# rgbboard.net
KiCad netlist of a schematic drawn in EAGLE
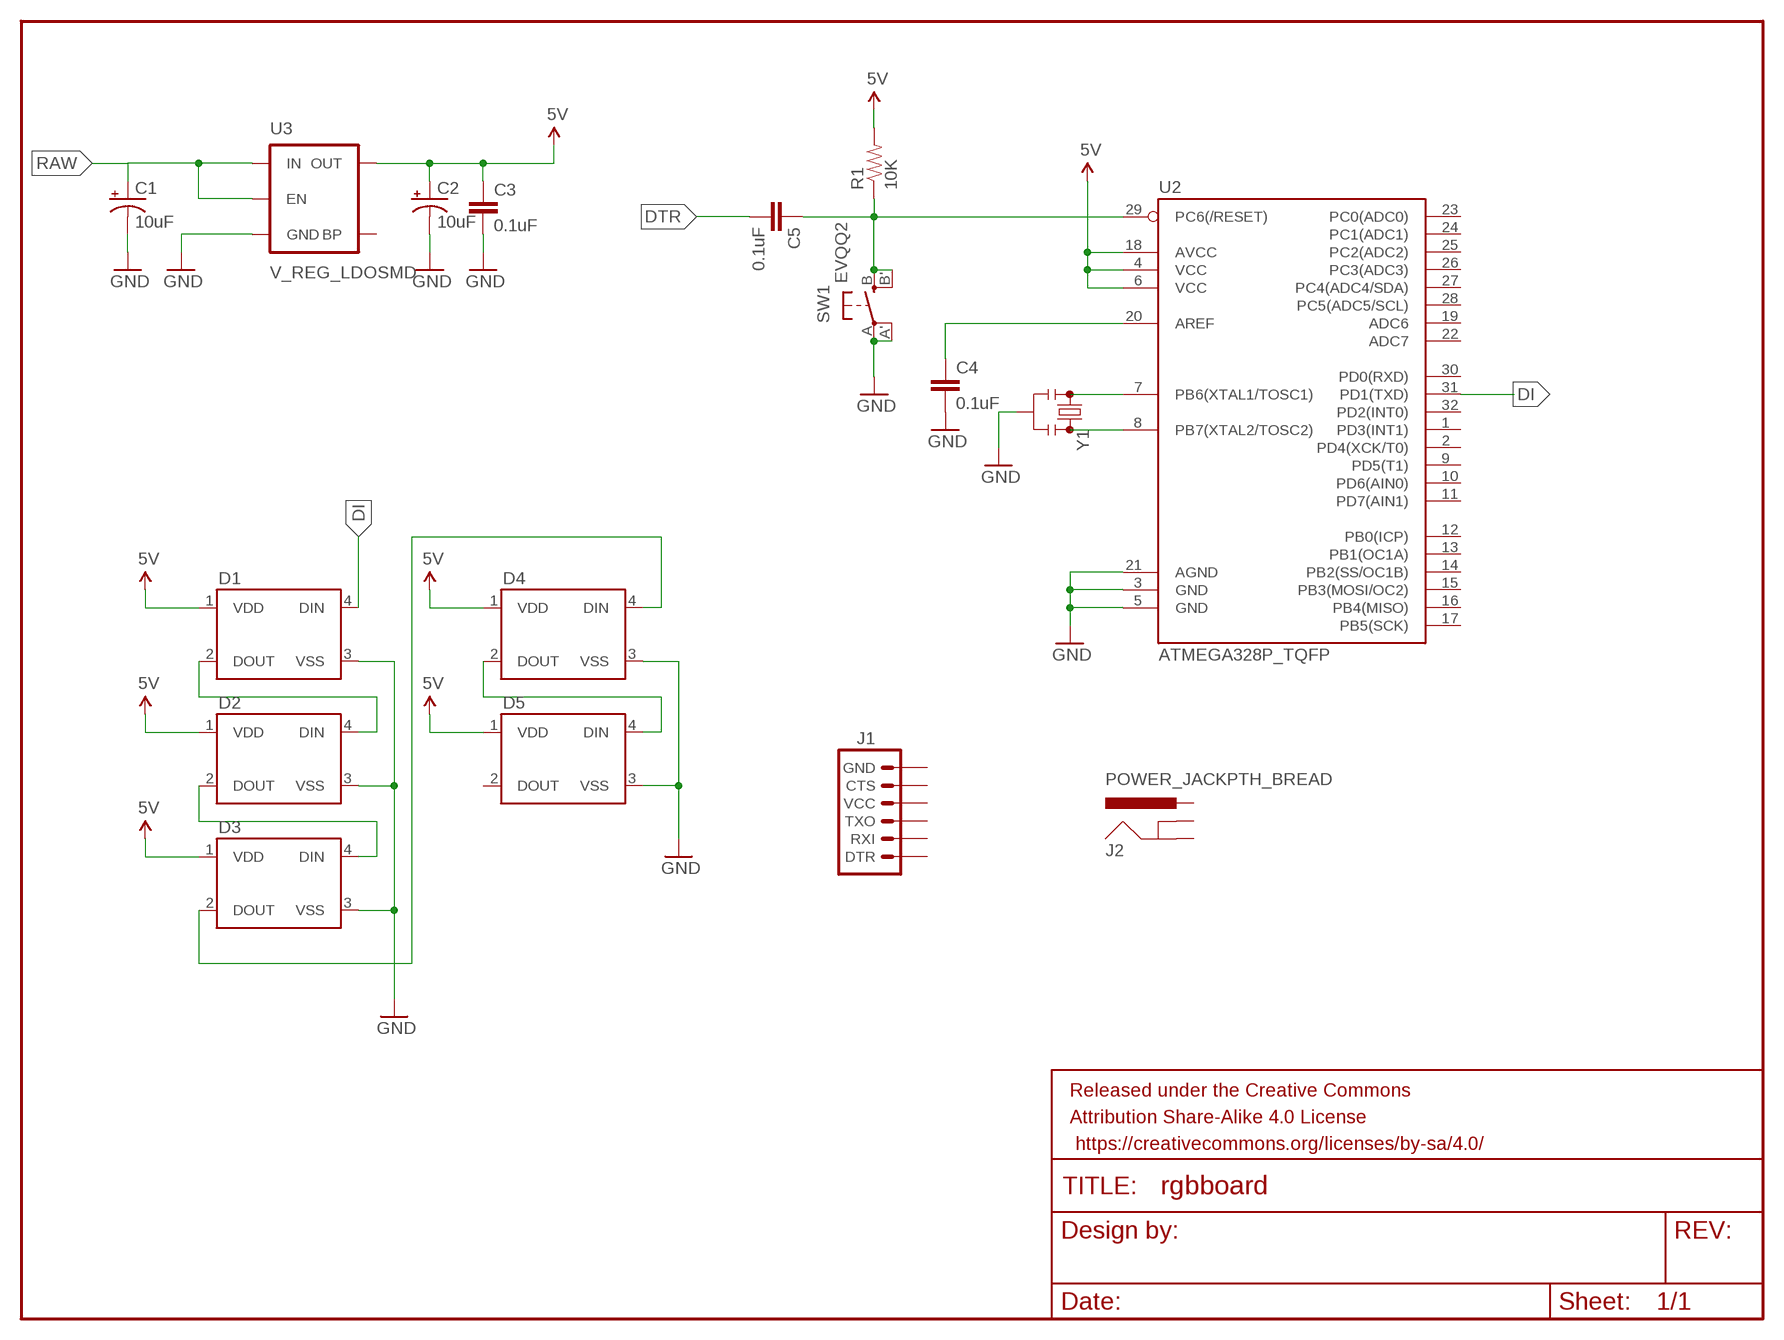
[diagram p0: schematic, sheet 1]

(export (version "E")
  (design (tool "Eeschema 10.0.6"))
  (components
    (comp (ref "C1")
      (value "10uF")
      (footprint "eagle-import:EIA3216")
      (libsource (lib "eagle-import") (part "CAP_POL1206"))
    )
    (comp (ref "C2")
      (value "10uF")
      (footprint "eagle-import:EIA3216")
      (libsource (lib "eagle-import") (part "CAP_POL1206"))
    )
    (comp (ref "C3")
      (value "0.1uF")
      (footprint "eagle-import:0603-CAP")
      (libsource (lib "eagle-import") (part "CAP0603-CAP"))
    )
    (comp (ref "C4")
      (value "0.1uF")
      (footprint "eagle-import:0603-CAP")
      (libsource (lib "eagle-import") (part "CAP0603-CAP"))
    )
    (comp (ref "C5")
      (value "0.1uF")
      (footprint "eagle-import:0603-CAP")
      (libsource (lib "eagle-import") (part "CAP0603-CAP"))
    )
    (comp (ref "D1")
      (value "WS2812B")
      (footprint "eagle-import:WS2812B")
      (libsource (lib "eagle-import") (part "WS2812B"))
    )
    (comp (ref "D2")
      (value "WS2812B")
      (footprint "eagle-import:WS2812B")
      (libsource (lib "eagle-import") (part "WS2812B"))
    )
    (comp (ref "D3")
      (value "WS2812B")
      (footprint "eagle-import:WS2812B")
      (libsource (lib "eagle-import") (part "WS2812B"))
    )
    (comp (ref "D4")
      (value "WS2812B")
      (footprint "eagle-import:WS2812B")
      (libsource (lib "eagle-import") (part "WS2812B"))
    )
    (comp (ref "D5")
      (value "WS2812B")
      (footprint "eagle-import:WS2812B")
      (libsource (lib "eagle-import") (part "WS2812B"))
    )
    (comp (ref "FRAME1")
      (value "FRAME-LETTER")
      (footprint "eagle-import:CREATIVE_COMMONS")
      (libsource (lib "eagle-import") (part "FRAME-LETTER"))
    )
    (comp (ref "J1")
      (value "ARDUINO_SERIAL_PROGRAMPTH")
      (footprint "eagle-import:1X06")
      (libsource (lib "eagle-import") (part "ARDUINO_SERIAL_PROGRAMPTH"))
    )
    (comp (ref "J2")
      (value "POWER_JACKPTH_BREAD")
      (footprint "eagle-import:POWER_JACK_PTH_BREAD")
      (libsource (lib "eagle-import") (part "POWER_JACKPTH_BREAD"))
    )
    (comp (ref "R1")
      (value "10K")
      (footprint "eagle-import:0603-RES")
      (libsource (lib "eagle-import") (part "RESISTOR0603"))
    )
    (comp (ref "SW1")
      (value "EVQQ2")
      (footprint "eagle-import:EVQ-Q2")
      (libsource (lib "eagle-import") (part "SPST_TACT-EVQQ2"))
    )
    (comp (ref "U2")
      (value "ATMEGA328P_TQFP")
      (footprint "eagle-import:TQFP32-08")
      (libsource (lib "eagle-import") (part "ATMEGA328P_TQFP"))
    )
    (comp (ref "U3")
      (value "V_REG_LDOSMD")
      (footprint "eagle-import:SOT23-5")
      (libsource (lib "eagle-import") (part "V_REG_LDOSMD"))
    )
    (comp (ref "Y1")
      (value "RESONATORPTH")
      (footprint "eagle-import:RESONATOR-PTH")
      (libsource (lib "eagle-import") (part "RESONATORPTH"))
    )
  )
  (nets
    (net (code "1") (name "5V") (class "Default")
      (node (ref "C2") (pin "A") (pinfunction "+_A") (pintype "passive"))
      (node (ref "C3") (pin "1") (pinfunction "1_1") (pintype "passive"))
      (node (ref "D1") (pin "1") (pinfunction "VDD_1") (pintype "power_in"))
      (node (ref "D2") (pin "1") (pinfunction "VDD_1") (pintype "power_in"))
      (node (ref "D3") (pin "1") (pinfunction "VDD_1") (pintype "power_in"))
      (node (ref "D4") (pin "1") (pinfunction "VDD_1") (pintype "power_in"))
      (node (ref "D5") (pin "1") (pinfunction "VDD_1") (pintype "power_in"))
      (node (ref "R1") (pin "2") (pinfunction "2_2") (pintype "passive"))
      (node (ref "U2") (pin "18") (pinfunction "AVCC_18") (pintype "bidirectional"))
      (node (ref "U2") (pin "4") (pinfunction "VCC_4") (pintype "bidirectional"))
      (node (ref "U2") (pin "6") (pinfunction "VCC_6") (pintype "bidirectional"))
      (node (ref "U3") (pin "5") (pinfunction "OUT_5") (pintype "passive"))
    )
    (net (code "2") (name "DI") (class "Default")
      (node (ref "D1") (pin "4") (pinfunction "DIN_4") (pintype "input"))
      (node (ref "U2") (pin "31") (pinfunction "PD1(TXD)_31") (pintype "bidirectional"))
    )
    (net (code "3") (name "DTR") (class "Default")
      (node (ref "C5") (pin "2") (pinfunction "2_2") (pintype "passive"))
    )
    (net (code "4") (name "GND") (class "Default")
      (node (ref "C1") (pin "C") (pinfunction "-_C") (pintype "passive"))
      (node (ref "C2") (pin "C") (pinfunction "-_C") (pintype "passive"))
      (node (ref "C3") (pin "2") (pinfunction "2_2") (pintype "passive"))
      (node (ref "C4") (pin "2") (pinfunction "2_2") (pintype "passive"))
      (node (ref "D1") (pin "3") (pinfunction "VSS_3") (pintype "power_in"))
      (node (ref "D2") (pin "3") (pinfunction "VSS_3") (pintype "power_in"))
      (node (ref "D3") (pin "3") (pinfunction "VSS_3") (pintype "power_in"))
      (node (ref "D4") (pin "3") (pinfunction "VSS_3") (pintype "power_in"))
      (node (ref "D5") (pin "3") (pinfunction "VSS_3") (pintype "power_in"))
      (node (ref "SW1") (pin "A") (pinfunction "P_A") (pintype "passive"))
      (node (ref "SW1") (pin "A'") (pinfunction "P1_A'") (pintype "passive"))
      (node (ref "U2") (pin "21") (pinfunction "AGND_21") (pintype "bidirectional"))
      (node (ref "U2") (pin "3") (pinfunction "GND_3") (pintype "bidirectional"))
      (node (ref "U2") (pin "5") (pinfunction "GND_5") (pintype "bidirectional"))
      (node (ref "U3") (pin "2") (pinfunction "GND_2") (pintype "input"))
      (node (ref "Y1") (pin "2") (pinfunction "2_2") (pintype "passive"))
    )
    (net (code "5") (name "Net-(D1-DOUT)") (class "Default")
      (node (ref "D1") (pin "2") (pinfunction "DOUT_2") (pintype "output"))
      (node (ref "D2") (pin "4") (pinfunction "DIN_4") (pintype "input"))
    )
    (net (code "6") (name "Net-(D2-DOUT)") (class "Default")
      (node (ref "D2") (pin "2") (pinfunction "DOUT_2") (pintype "output"))
      (node (ref "D3") (pin "4") (pinfunction "DIN_4") (pintype "input"))
    )
    (net (code "7") (name "Net-(D3-DOUT)") (class "Default")
      (node (ref "D3") (pin "2") (pinfunction "DOUT_2") (pintype "output"))
      (node (ref "D4") (pin "4") (pinfunction "DIN_4") (pintype "input"))
    )
    (net (code "8") (name "Net-(D4-DOUT)") (class "Default")
      (node (ref "D4") (pin "2") (pinfunction "DOUT_2") (pintype "output"))
      (node (ref "D5") (pin "4") (pinfunction "DIN_4") (pintype "input"))
    )
    (net (code "9") (name "Net-(SW1-S)") (class "Default")
      (node (ref "C5") (pin "1") (pinfunction "1_1") (pintype "passive"))
      (node (ref "R1") (pin "1") (pinfunction "1_1") (pintype "passive"))
      (node (ref "SW1") (pin "B") (pinfunction "S_B") (pintype "passive"))
      (node (ref "SW1") (pin "B'") (pinfunction "S1_B'") (pintype "passive"))
      (node (ref "U2") (pin "29") (pinfunction "PC6(/RESET)_29") (pintype "bidirectional"))
    )
    (net (code "10") (name "Net-(U2-AREF)") (class "Default")
      (node (ref "C4") (pin "1") (pinfunction "1_1") (pintype "passive"))
      (node (ref "U2") (pin "20") (pinfunction "AREF_20") (pintype "bidirectional"))
    )
    (net (code "11") (name "Net-(U2-PB6(XTAL1{slash}TOSC1))") (class "Default")
      (node (ref "U2") (pin "7") (pinfunction "PB6(XTAL1/TOSC1)_7") (pintype "bidirectional"))
      (node (ref "Y1") (pin "1") (pinfunction "1_1") (pintype "passive"))
    )
    (net (code "12") (name "Net-(U2-PB7(XTAL2{slash}TOSC2))") (class "Default")
      (node (ref "U2") (pin "8") (pinfunction "PB7(XTAL2/TOSC2)_8") (pintype "bidirectional"))
      (node (ref "Y1") (pin "3") (pinfunction "3_3") (pintype "passive"))
    )
    (net (code "13") (name "RAW") (class "Default")
      (node (ref "C1") (pin "A") (pinfunction "+_A") (pintype "passive"))
      (node (ref "U3") (pin "1") (pinfunction "IN_1") (pintype "input"))
      (node (ref "U3") (pin "3") (pinfunction "EN_3") (pintype "input"))
    )
    (net (code "14") (name "unconnected-(D5-DOUT-Pad2)") (class "Default")
      (node (ref "D5") (pin "2") (pinfunction "DOUT_2") (pintype "output"))
    )
    (net (code "15") (name "unconnected-(J1-CTS-Pad5)") (class "Default")
      (node (ref "J1") (pin "5") (pinfunction "CTS_5") (pintype "passive"))
    )
    (net (code "16") (name "unconnected-(J1-DTR-Pad1)") (class "Default")
      (node (ref "J1") (pin "1") (pinfunction "DTR_1") (pintype "passive"))
    )
    (net (code "17") (name "unconnected-(J1-GND-Pad6)") (class "Default")
      (node (ref "J1") (pin "6") (pinfunction "GND_6") (pintype "passive"))
    )
    (net (code "18") (name "unconnected-(J1-RXI-Pad2)") (class "Default")
      (node (ref "J1") (pin "2") (pinfunction "RXI_2") (pintype "passive"))
    )
    (net (code "19") (name "unconnected-(J1-TXO-Pad3)") (class "Default")
      (node (ref "J1") (pin "3") (pinfunction "TXO_3") (pintype "passive"))
    )
    (net (code "20") (name "unconnected-(J1-VCC-Pad4)") (class "Default")
      (node (ref "J1") (pin "4") (pinfunction "VCC_4") (pintype "passive"))
    )
    (net (code "21") (name "unconnected-(J2-PadGND)") (class "Default")
      (node (ref "J2") (pin "GND") (pinfunction "GND_GND") (pintype "bidirectional"))
    )
    (net (code "22") (name "unconnected-(J2-PadGNDBREAK)") (class "Default")
      (node (ref "J2") (pin "GNDBREAK") (pinfunction "GNDBREAK_GNDBREAK") (pintype "bidirectional"))
    )
    (net (code "23") (name "unconnected-(J2-PadPWR)") (class "Default")
      (node (ref "J2") (pin "PWR") (pinfunction "PWR_PWR") (pintype "bidirectional"))
    )
    (net (code "24") (name "unconnected-(U2-ADC6-Pad19)") (class "Default")
      (node (ref "U2") (pin "19") (pinfunction "ADC6_19") (pintype "bidirectional"))
    )
    (net (code "25") (name "unconnected-(U2-ADC7-Pad22)") (class "Default")
      (node (ref "U2") (pin "22") (pinfunction "ADC7_22") (pintype "bidirectional"))
    )
    (net (code "26") (name "unconnected-(U2-PB0(ICP)-Pad12)") (class "Default")
      (node (ref "U2") (pin "12") (pinfunction "PB0(ICP)_12") (pintype "bidirectional"))
    )
    (net (code "27") (name "unconnected-(U2-PB1(OC1A)-Pad13)") (class "Default")
      (node (ref "U2") (pin "13") (pinfunction "PB1(OC1A)_13") (pintype "bidirectional"))
    )
    (net (code "28") (name "unconnected-(U2-PB2(SS{slash}OC1B)-Pad14)") (class "Default")
      (node (ref "U2") (pin "14") (pinfunction "PB2(SS/OC1B)_14") (pintype "bidirectional"))
    )
    (net (code "29") (name "unconnected-(U2-PB3(MOSI{slash}OC2)-Pad15)") (class "Default")
      (node (ref "U2") (pin "15") (pinfunction "PB3(MOSI/OC2)_15") (pintype "bidirectional"))
    )
    (net (code "30") (name "unconnected-(U2-PB4(MISO)-Pad16)") (class "Default")
      (node (ref "U2") (pin "16") (pinfunction "PB4(MISO)_16") (pintype "bidirectional"))
    )
    (net (code "31") (name "unconnected-(U2-PB5(SCK)-Pad17)") (class "Default")
      (node (ref "U2") (pin "17") (pinfunction "PB5(SCK)_17") (pintype "bidirectional"))
    )
    (net (code "32") (name "unconnected-(U2-PC0(ADC0)-Pad23)") (class "Default")
      (node (ref "U2") (pin "23") (pinfunction "PC0(ADC0)_23") (pintype "bidirectional"))
    )
    (net (code "33") (name "unconnected-(U2-PC1(ADC1)-Pad24)") (class "Default")
      (node (ref "U2") (pin "24") (pinfunction "PC1(ADC1)_24") (pintype "bidirectional"))
    )
    (net (code "34") (name "unconnected-(U2-PC2(ADC2)-Pad25)") (class "Default")
      (node (ref "U2") (pin "25") (pinfunction "PC2(ADC2)_25") (pintype "bidirectional"))
    )
    (net (code "35") (name "unconnected-(U2-PC3(ADC3)-Pad26)") (class "Default")
      (node (ref "U2") (pin "26") (pinfunction "PC3(ADC3)_26") (pintype "bidirectional"))
    )
    (net (code "36") (name "unconnected-(U2-PC4(ADC4{slash}SDA)-Pad27)") (class "Default")
      (node (ref "U2") (pin "27") (pinfunction "PC4(ADC4/SDA)_27") (pintype "bidirectional"))
    )
    (net (code "37") (name "unconnected-(U2-PC5(ADC5{slash}SCL)-Pad28)") (class "Default")
      (node (ref "U2") (pin "28") (pinfunction "PC5(ADC5/SCL)_28") (pintype "bidirectional"))
    )
    (net (code "38") (name "unconnected-(U2-PD0(RXD)-Pad30)") (class "Default")
      (node (ref "U2") (pin "30") (pinfunction "PD0(RXD)_30") (pintype "bidirectional"))
    )
    (net (code "39") (name "unconnected-(U2-PD2(INT0)-Pad32)") (class "Default")
      (node (ref "U2") (pin "32") (pinfunction "PD2(INT0)_32") (pintype "bidirectional"))
    )
    (net (code "40") (name "unconnected-(U2-PD3(INT1)-Pad1)") (class "Default")
      (node (ref "U2") (pin "1") (pinfunction "PD3(INT1)_1") (pintype "bidirectional"))
    )
    (net (code "41") (name "unconnected-(U2-PD4(XCK{slash}T0)-Pad2)") (class "Default")
      (node (ref "U2") (pin "2") (pinfunction "PD4(XCK/T0)_2") (pintype "bidirectional"))
    )
    (net (code "42") (name "unconnected-(U2-PD5(T1)-Pad9)") (class "Default")
      (node (ref "U2") (pin "9") (pinfunction "PD5(T1)_9") (pintype "bidirectional"))
    )
    (net (code "43") (name "unconnected-(U2-PD6(AIN0)-Pad10)") (class "Default")
      (node (ref "U2") (pin "10") (pinfunction "PD6(AIN0)_10") (pintype "bidirectional"))
    )
    (net (code "44") (name "unconnected-(U2-PD7(AIN1)-Pad11)") (class "Default")
      (node (ref "U2") (pin "11") (pinfunction "PD7(AIN1)_11") (pintype "bidirectional"))
    )
    (net (code "45") (name "unconnected-(U3-BP-Pad4)") (class "Default")
      (node (ref "U3") (pin "4") (pinfunction "BP_4") (pintype "input"))
    )
  )
)
